# schematic7.net
KiCad netlist of a schematic drawn in Altium Designer
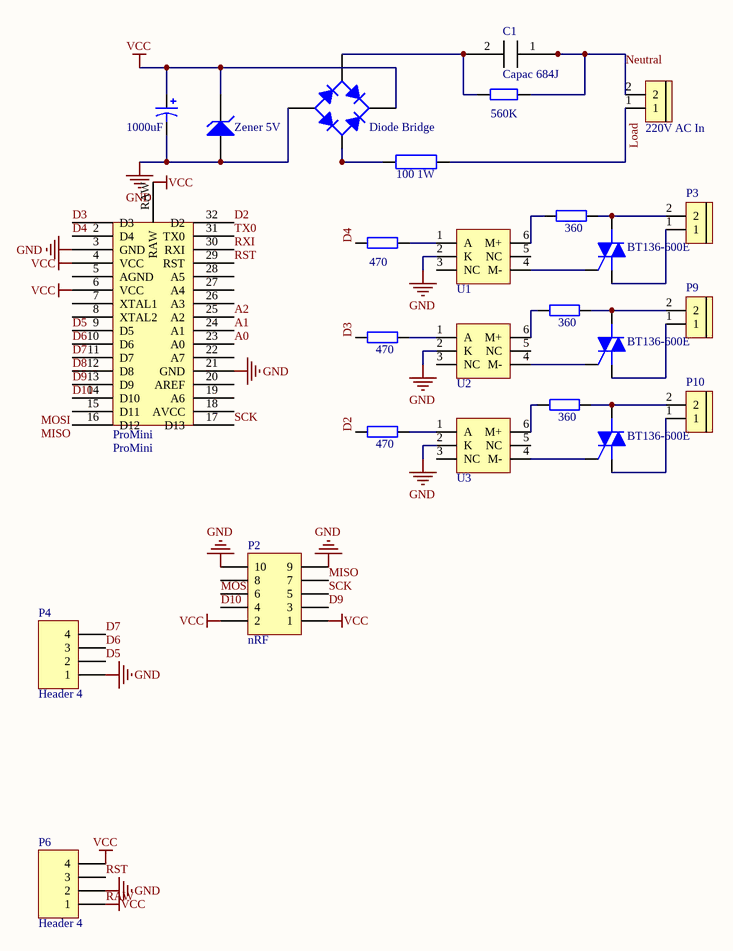
[diagram p0: schematic7.SchDoc]

(export (version "E")
  (design (tool "Eeschema 10.0.6"))
  (components
    (comp (ref "C1")
      (value "Capac 684J")
      (footprint "Tu keo 684J 400V")
      (libsource (lib "ArduinoLib") (part "Tu keo 684J 400V"))
    )
    (comp (ref "C3")
      (value "1000uF")
      (footprint "C10mm")
      (description "Polarized Capacitor (Axial)")
      (fields (field (name "PUBLISHER") "Altium Limited"))
      (libsource (lib "NBBLib 14-03-2012") (part "Cap Pol 8mm"))
    )
    (comp (ref "D1")
      (value "Diode Bridge")
      (footprint "D-38")
      (description "Full Wave Diode Bridge")
      (fields (field (name "PUBLISHER") "Altium Limited"))
      (libsource (lib "Miscellaneous Devices") (part "Bridge1"))
    )
    (comp (ref "D3")
      (value "Zener 5V")
      (footprint "DIODE/NOM/0.5A")
      (description "Zener Diode")
      (fields (field (name "VOLTAGE") "5") (field (name "PUBLISHER") "Altium Limited"))
      (libsource (lib "NBBLib 14-03-2012") (part "Diode Zener"))
    )
    (comp (ref "P1")
      (value "220V AC In")
      (footprint "BIG_Header 2")
      (libsource (lib "NBBLib 14-03-2012") (part "BIG_Header 2"))
    )
    (comp (ref "P2")
      (value "nRF")
      (footprint "HDR2X5")
      (description "Header, 5-Pin, Dual row")
      (fields (field (name "PUBLISHER") "Altium Limited"))
      (libsource (lib "Miscellaneous Connectors") (part "Header 5X2"))
    )
    (comp (ref "P3")
      (value "BIG_Header 2")
      (footprint "BIG_Header 2")
      (libsource (lib "NBBLib 14-03-2012") (part "BIG_Header 2"))
    )
    (comp (ref "P4")
      (value "Header 4")
      (footprint "HDR1X4")
      (description "Header, 4-Pin")
      (fields (field (name "PUBLISHER") "Altium Limited"))
      (libsource (lib "Miscellaneous Connectors") (part "Header 4"))
    )
    (comp (ref "P6")
      (value "Header 4")
      (footprint "HDR1X4")
      (description "Header, 4-Pin")
      (fields (field (name "PUBLISHER") "Altium Limited"))
      (libsource (lib "Miscellaneous Connectors") (part "Header 4"))
    )
    (comp (ref "P9")
      (value "BIG_Header 2")
      (footprint "BIG_Header 2")
      (libsource (lib "NBBLib 14-03-2012") (part "BIG_Header 2"))
    )
    (comp (ref "P10")
      (value "BIG_Header 2")
      (footprint "BIG_Header 2")
      (libsource (lib "NBBLib 14-03-2012") (part "BIG_Header 2"))
    )
    (comp (ref "ProMini")
      (value "ProMini")
      (footprint "Arduino Pro Mini")
      (libsource (lib "ArduinoLib") (part "Pro Mini"))
    )
    (comp (ref "Q1")
      (value "BT136-600E")
      (footprint "BTA6-600")
      (description "Silicon Bidirectional Triode Thyristor")
      (fields (field (name "PUBLISHER") "Altium Limited"))
      (libsource (lib "NBBLib 14-03-2012") (part "BTA12-600"))
    )
    (comp (ref "Q2")
      (value "BT136-600E")
      (footprint "BTA6-600")
      (description "Silicon Bidirectional Triode Thyristor")
      (fields (field (name "PUBLISHER") "Altium Limited"))
      (libsource (lib "NBBLib 14-03-2012") (part "BTA12-600"))
    )
    (comp (ref "Q3")
      (value "BT136-600E")
      (footprint "BTA6-600")
      (description "Silicon Bidirectional Triode Thyristor")
      (fields (field (name "PUBLISHER") "Altium Limited"))
      (libsource (lib "NBBLib 14-03-2012") (part "BTA12-600"))
    )
    (comp (ref "R1")
      (value "100 1W")
      (footprint "DIEN TRO 1W (tube)")
      (description "1W Res Power")
      (fields (field (name "VOLTAGE") "400") (field (name "CREATOR") "Nguyen Ba Bien"))
      (libsource (lib "NBBLib 14-03-2012") (part "Res 1W"))
    )
    (comp (ref "R3")
      (value "560K")
      (footprint "AXIAL-0.4")
      (description "Resistor")
      (fields (field (name "PUBLISHER") "Altium Limited"))
      (libsource (lib "Miscellaneous Devices") (part "Res2"))
    )
    (comp (ref "R4")
      (value "470")
      (footprint "R1/4W")
      (description "Resistor")
      (libsource (lib "t.thien") (part "R1/4W"))
    )
    (comp (ref "R5")
      (value "360")
      (footprint "R1/4W")
      (description "Resistor")
      (libsource (lib "t.thien") (part "R1/4W"))
    )
    (comp (ref "R7")
      (value "470")
      (footprint "R1/4W")
      (description "Resistor")
      (libsource (lib "t.thien") (part "R1/4W"))
    )
    (comp (ref "R8")
      (value "360")
      (footprint "R1/4W")
      (description "Resistor")
      (libsource (lib "t.thien") (part "R1/4W"))
    )
    (comp (ref "R9")
      (value "470")
      (footprint "R1/4W")
      (description "Resistor")
      (libsource (lib "t.thien") (part "R1/4W"))
    )
    (comp (ref "R10")
      (value "360")
      (footprint "R1/4W")
      (description "Resistor")
      (libsource (lib "t.thien") (part "R1/4W"))
    )
    (comp (ref "U1")
      (value "MOC3021M")
      (footprint "MOC30XX")
      (libsource (lib "NBBLib 14-03-2012") (part "MOC3021M"))
    )
    (comp (ref "U2")
      (value "MOC3021M")
      (footprint "MOC30XX")
      (libsource (lib "NBBLib 14-03-2012") (part "MOC3021M"))
    )
    (comp (ref "U3")
      (value "MOC3021M")
      (footprint "MOC30XX")
      (libsource (lib "NBBLib 14-03-2012") (part "MOC3021M"))
    )
  )
  (nets
    (net (code "1") (name "/A0") (class "Default")
      (node (ref "ProMini") (pin "23") (pinfunction "A0_23") (pintype "passive"))
    )
    (net (code "2") (name "/A1") (class "Default")
      (node (ref "ProMini") (pin "24") (pinfunction "A1_24") (pintype "passive"))
    )
    (net (code "3") (name "/A2") (class "Default")
      (node (ref "ProMini") (pin "25") (pinfunction "A2_25") (pintype "passive"))
    )
    (net (code "4") (name "/D2") (class "Default")
      (node (ref "ProMini") (pin "32") (pinfunction "D2_32") (pintype "passive"))
      (node (ref "R9") (pin "1") (pinfunction "1_1") (pintype "passive"))
    )
    (net (code "5") (name "/D3") (class "Default")
      (node (ref "ProMini") (pin "1") (pinfunction "D3_1") (pintype "passive"))
      (node (ref "R7") (pin "1") (pinfunction "1_1") (pintype "passive"))
    )
    (net (code "6") (name "/D4") (class "Default")
      (node (ref "ProMini") (pin "2") (pinfunction "D4_2") (pintype "passive"))
      (node (ref "R4") (pin "1") (pinfunction "1_1") (pintype "passive"))
    )
    (net (code "7") (name "/D5") (class "Default")
      (node (ref "P4") (pin "2") (pinfunction "2_2") (pintype "passive"))
      (node (ref "ProMini") (pin "9") (pinfunction "D5_9") (pintype "passive"))
    )
    (net (code "8") (name "/D6") (class "Default")
      (node (ref "P4") (pin "3") (pinfunction "3_3") (pintype "passive"))
      (node (ref "ProMini") (pin "10") (pinfunction "D6_10") (pintype "passive"))
    )
    (net (code "9") (name "/D7") (class "Default")
      (node (ref "P4") (pin "4") (pinfunction "4_4") (pintype "passive"))
      (node (ref "ProMini") (pin "11") (pinfunction "D7_11") (pintype "passive"))
    )
    (net (code "10") (name "/D8") (class "Default")
      (node (ref "ProMini") (pin "12") (pinfunction "D8_12") (pintype "passive"))
    )
    (net (code "11") (name "/D9") (class "Default")
      (node (ref "P2") (pin "3") (pinfunction "3_3") (pintype "passive"))
      (node (ref "ProMini") (pin "13") (pinfunction "D9_13") (pintype "passive"))
    )
    (net (code "12") (name "/D10") (class "Default")
      (node (ref "P2") (pin "4") (pinfunction "4_4") (pintype "passive"))
      (node (ref "ProMini") (pin "14") (pinfunction "D10_14") (pintype "passive"))
    )
    (net (code "13") (name "/Load") (class "Default")
      (node (ref "P1") (pin "1") (pinfunction "1_1") (pintype "passive"))
      (node (ref "R1") (pin "2") (pinfunction "2_2") (pintype "passive"))
    )
    (net (code "14") (name "/MISO") (class "Default")
      (node (ref "P2") (pin "7") (pinfunction "7_7") (pintype "passive"))
      (node (ref "ProMini") (pin "16") (pinfunction "D12_16") (pintype "passive"))
    )
    (net (code "15") (name "/MOSI") (class "Default")
      (node (ref "P2") (pin "6") (pinfunction "6_6") (pintype "passive"))
      (node (ref "ProMini") (pin "15") (pinfunction "D11_15") (pintype "passive"))
    )
    (net (code "16") (name "/Neutral") (class "Default")
      (node (ref "C1") (pin "1") (pinfunction "1_1") (pintype "passive"))
      (node (ref "P1") (pin "2") (pinfunction "2_2") (pintype "passive"))
      (node (ref "R3") (pin "2") (pinfunction "2_2") (pintype "passive"))
    )
    (net (code "17") (name "/RST") (class "Default")
      (node (ref "P6") (pin "3") (pinfunction "3_3") (pintype "passive"))
      (node (ref "ProMini") (pin "29") (pinfunction "RST_29") (pintype "passive"))
    )
    (net (code "18") (name "/RXI") (class "Default")
      (node (ref "ProMini") (pin "30") (pinfunction "RXI_30") (pintype "passive"))
    )
    (net (code "19") (name "/SCK") (class "Default")
      (node (ref "P2") (pin "5") (pinfunction "5_5") (pintype "passive"))
      (node (ref "ProMini") (pin "17") (pinfunction "D13_17") (pintype "passive"))
    )
    (net (code "20") (name "/TX0") (class "Default")
      (node (ref "ProMini") (pin "31") (pinfunction "TX0_31") (pintype "passive"))
    )
    (net (code "21") (name "GND") (class "Default")
      (node (ref "C3") (pin "2") (pinfunction "2_2") (pintype "passive"))
      (node (ref "D1") (pin "3") (pinfunction "A_3") (pintype "passive"))
      (node (ref "D3") (pin "1") (pinfunction "A_1") (pintype "passive"))
      (node (ref "P2") (pin "10") (pinfunction "10_10") (pintype "passive"))
      (node (ref "P2") (pin "9") (pinfunction "9_9") (pintype "passive"))
      (node (ref "P4") (pin "1") (pinfunction "1_1") (pintype "passive"))
      (node (ref "P6") (pin "2") (pinfunction "2_2") (pintype "passive"))
      (node (ref "ProMini") (pin "21") (pinfunction "GND_21") (pintype "passive"))
      (node (ref "ProMini") (pin "3") (pinfunction "GND_3") (pintype "passive"))
      (node (ref "U1") (pin "2") (pinfunction "K_2") (pintype "passive"))
      (node (ref "U2") (pin "2") (pinfunction "K_2") (pintype "passive"))
      (node (ref "U3") (pin "2") (pinfunction "K_2") (pintype "passive"))
    )
    (net (code "22") (name "Net-(C1-Pad2)") (class "Default")
      (node (ref "C1") (pin "2") (pinfunction "2_2") (pintype "passive"))
      (node (ref "D1") (pin "4") (pinfunction "C_4") (pintype "passive"))
      (node (ref "R3") (pin "1") (pinfunction "1_1") (pintype "passive"))
    )
    (net (code "23") (name "Net-(D1-C-Pad2)") (class "Default")
      (node (ref "D1") (pin "2") (pinfunction "C_2") (pintype "passive"))
      (node (ref "R1") (pin "1") (pinfunction "1_1") (pintype "passive"))
    )
    (net (code "24") (name "Net-(Q1-G)") (class "Default")
      (node (ref "Q1") (pin "3") (pinfunction "G_3") (pintype "passive"))
      (node (ref "U1") (pin "4") (pinfunction "M-_4") (pintype "passive"))
    )
    (net (code "25") (name "Net-(Q1-M1)") (class "Default")
      (node (ref "P3") (pin "1") (pinfunction "1_1") (pintype "passive"))
      (node (ref "Q1") (pin "1") (pinfunction "M1_1") (pintype "passive"))
    )
    (net (code "26") (name "Net-(Q1-M2)") (class "Default")
      (node (ref "P3") (pin "2") (pinfunction "2_2") (pintype "passive"))
      (node (ref "Q1") (pin "2") (pinfunction "M2_2") (pintype "passive"))
      (node (ref "R5") (pin "2") (pinfunction "2_2") (pintype "passive"))
    )
    (net (code "27") (name "Net-(Q2-G)") (class "Default")
      (node (ref "Q2") (pin "3") (pinfunction "G_3") (pintype "passive"))
      (node (ref "U2") (pin "4") (pinfunction "M-_4") (pintype "passive"))
    )
    (net (code "28") (name "Net-(Q2-M1)") (class "Default")
      (node (ref "P9") (pin "1") (pinfunction "1_1") (pintype "passive"))
      (node (ref "Q2") (pin "1") (pinfunction "M1_1") (pintype "passive"))
    )
    (net (code "29") (name "Net-(Q2-M2)") (class "Default")
      (node (ref "P9") (pin "2") (pinfunction "2_2") (pintype "passive"))
      (node (ref "Q2") (pin "2") (pinfunction "M2_2") (pintype "passive"))
      (node (ref "R8") (pin "2") (pinfunction "2_2") (pintype "passive"))
    )
    (net (code "30") (name "Net-(Q3-G)") (class "Default")
      (node (ref "Q3") (pin "3") (pinfunction "G_3") (pintype "passive"))
      (node (ref "U3") (pin "4") (pinfunction "M-_4") (pintype "passive"))
    )
    (net (code "31") (name "Net-(Q3-M1)") (class "Default")
      (node (ref "P10") (pin "1") (pinfunction "1_1") (pintype "passive"))
      (node (ref "Q3") (pin "1") (pinfunction "M1_1") (pintype "passive"))
    )
    (net (code "32") (name "Net-(Q3-M2)") (class "Default")
      (node (ref "P10") (pin "2") (pinfunction "2_2") (pintype "passive"))
      (node (ref "Q3") (pin "2") (pinfunction "M2_2") (pintype "passive"))
      (node (ref "R10") (pin "2") (pinfunction "2_2") (pintype "passive"))
    )
    (net (code "33") (name "Net-(U1-A)") (class "Default")
      (node (ref "R4") (pin "2") (pinfunction "2_2") (pintype "passive"))
      (node (ref "U1") (pin "1") (pinfunction "A_1") (pintype "passive"))
    )
    (net (code "34") (name "Net-(U1-M+)") (class "Default")
      (node (ref "R5") (pin "1") (pinfunction "1_1") (pintype "passive"))
      (node (ref "U1") (pin "6") (pinfunction "M+_6") (pintype "passive"))
    )
    (net (code "35") (name "Net-(U2-A)") (class "Default")
      (node (ref "R7") (pin "2") (pinfunction "2_2") (pintype "passive"))
      (node (ref "U2") (pin "1") (pinfunction "A_1") (pintype "passive"))
    )
    (net (code "36") (name "Net-(U2-M+)") (class "Default")
      (node (ref "R8") (pin "1") (pinfunction "1_1") (pintype "passive"))
      (node (ref "U2") (pin "6") (pinfunction "M+_6") (pintype "passive"))
    )
    (net (code "37") (name "Net-(U3-A)") (class "Default")
      (node (ref "R9") (pin "2") (pinfunction "2_2") (pintype "passive"))
      (node (ref "U3") (pin "1") (pinfunction "A_1") (pintype "passive"))
    )
    (net (code "38") (name "Net-(U3-M+)") (class "Default")
      (node (ref "R10") (pin "1") (pinfunction "1_1") (pintype "passive"))
      (node (ref "U3") (pin "6") (pinfunction "M+_6") (pintype "passive"))
    )
    (net (code "39") (name "VCC") (class "Default")
      (node (ref "C3") (pin "1") (pinfunction "1_1") (pintype "passive"))
      (node (ref "D1") (pin "1") (pinfunction "K_1") (pintype "passive"))
      (node (ref "D3") (pin "2") (pinfunction "K_2") (pintype "passive"))
      (node (ref "P2") (pin "1") (pinfunction "1_1") (pintype "passive"))
      (node (ref "P2") (pin "2") (pinfunction "2_2") (pintype "passive"))
      (node (ref "P6") (pin "1") (pinfunction "1_1") (pintype "passive"))
      (node (ref "P6") (pin "4") (pinfunction "4_4") (pintype "passive"))
      (node (ref "ProMini") (pin "4") (pinfunction "VCC_4") (pintype "passive"))
      (node (ref "ProMini") (pin "6") (pinfunction "VCC_6") (pintype "passive"))
      (node (ref "ProMini") (pin "RAW") (pinfunction "RAW_RAW") (pintype "passive"))
    )
    (net (code "40") (name "unconnected-(P2-Pad8)") (class "Default")
      (node (ref "P2") (pin "8") (pinfunction "8_8") (pintype "passive"))
    )
    (net (code "41") (name "unconnected-(ProMini-A3-Pad26)") (class "Default")
      (node (ref "ProMini") (pin "26") (pinfunction "A3_26") (pintype "passive"))
    )
    (net (code "42") (name "unconnected-(ProMini-A4-Pad27)") (class "Default")
      (node (ref "ProMini") (pin "27") (pinfunction "A4_27") (pintype "passive"))
    )
    (net (code "43") (name "unconnected-(ProMini-A5-Pad28)") (class "Default")
      (node (ref "ProMini") (pin "28") (pinfunction "A5_28") (pintype "passive"))
    )
    (net (code "44") (name "unconnected-(ProMini-A6-Pad19)") (class "Default")
      (node (ref "ProMini") (pin "19") (pinfunction "A6_19") (pintype "passive"))
    )
    (net (code "45") (name "unconnected-(ProMini-A7-Pad22)") (class "Default")
      (node (ref "ProMini") (pin "22") (pinfunction "A7_22") (pintype "passive"))
    )
    (net (code "46") (name "unconnected-(ProMini-AGND-Pad5)") (class "Default")
      (node (ref "ProMini") (pin "5") (pinfunction "AGND_5") (pintype "passive"))
    )
    (net (code "47") (name "unconnected-(ProMini-AREF-Pad20)") (class "Default")
      (node (ref "ProMini") (pin "20") (pinfunction "AREF_20") (pintype "passive"))
    )
    (net (code "48") (name "unconnected-(ProMini-AVCC-Pad18)") (class "Default")
      (node (ref "ProMini") (pin "18") (pinfunction "AVCC_18") (pintype "passive"))
    )
    (net (code "49") (name "unconnected-(ProMini-XTAL1-Pad7)") (class "Default")
      (node (ref "ProMini") (pin "7") (pinfunction "XTAL1_7") (pintype "passive"))
    )
    (net (code "50") (name "unconnected-(ProMini-XTAL2-Pad8)") (class "Default")
      (node (ref "ProMini") (pin "8") (pinfunction "XTAL2_8") (pintype "passive"))
    )
    (net (code "51") (name "unconnected-(U1-NC-Pad3)") (class "Default")
      (node (ref "U1") (pin "3") (pinfunction "NC_3") (pintype "passive"))
    )
    (net (code "52") (name "unconnected-(U1-NC-Pad5)") (class "Default")
      (node (ref "U1") (pin "5") (pinfunction "NC_5") (pintype "passive"))
    )
    (net (code "53") (name "unconnected-(U2-NC-Pad3)") (class "Default")
      (node (ref "U2") (pin "3") (pinfunction "NC_3") (pintype "passive"))
    )
    (net (code "54") (name "unconnected-(U2-NC-Pad5)") (class "Default")
      (node (ref "U2") (pin "5") (pinfunction "NC_5") (pintype "passive"))
    )
    (net (code "55") (name "unconnected-(U3-NC-Pad3)") (class "Default")
      (node (ref "U3") (pin "3") (pinfunction "NC_3") (pintype "passive"))
    )
    (net (code "56") (name "unconnected-(U3-NC-Pad5)") (class "Default")
      (node (ref "U3") (pin "5") (pinfunction "NC_5") (pintype "passive"))
    )
  )
)
